# hbs.net
KiCad netlist of a schematic drawn in EAGLE
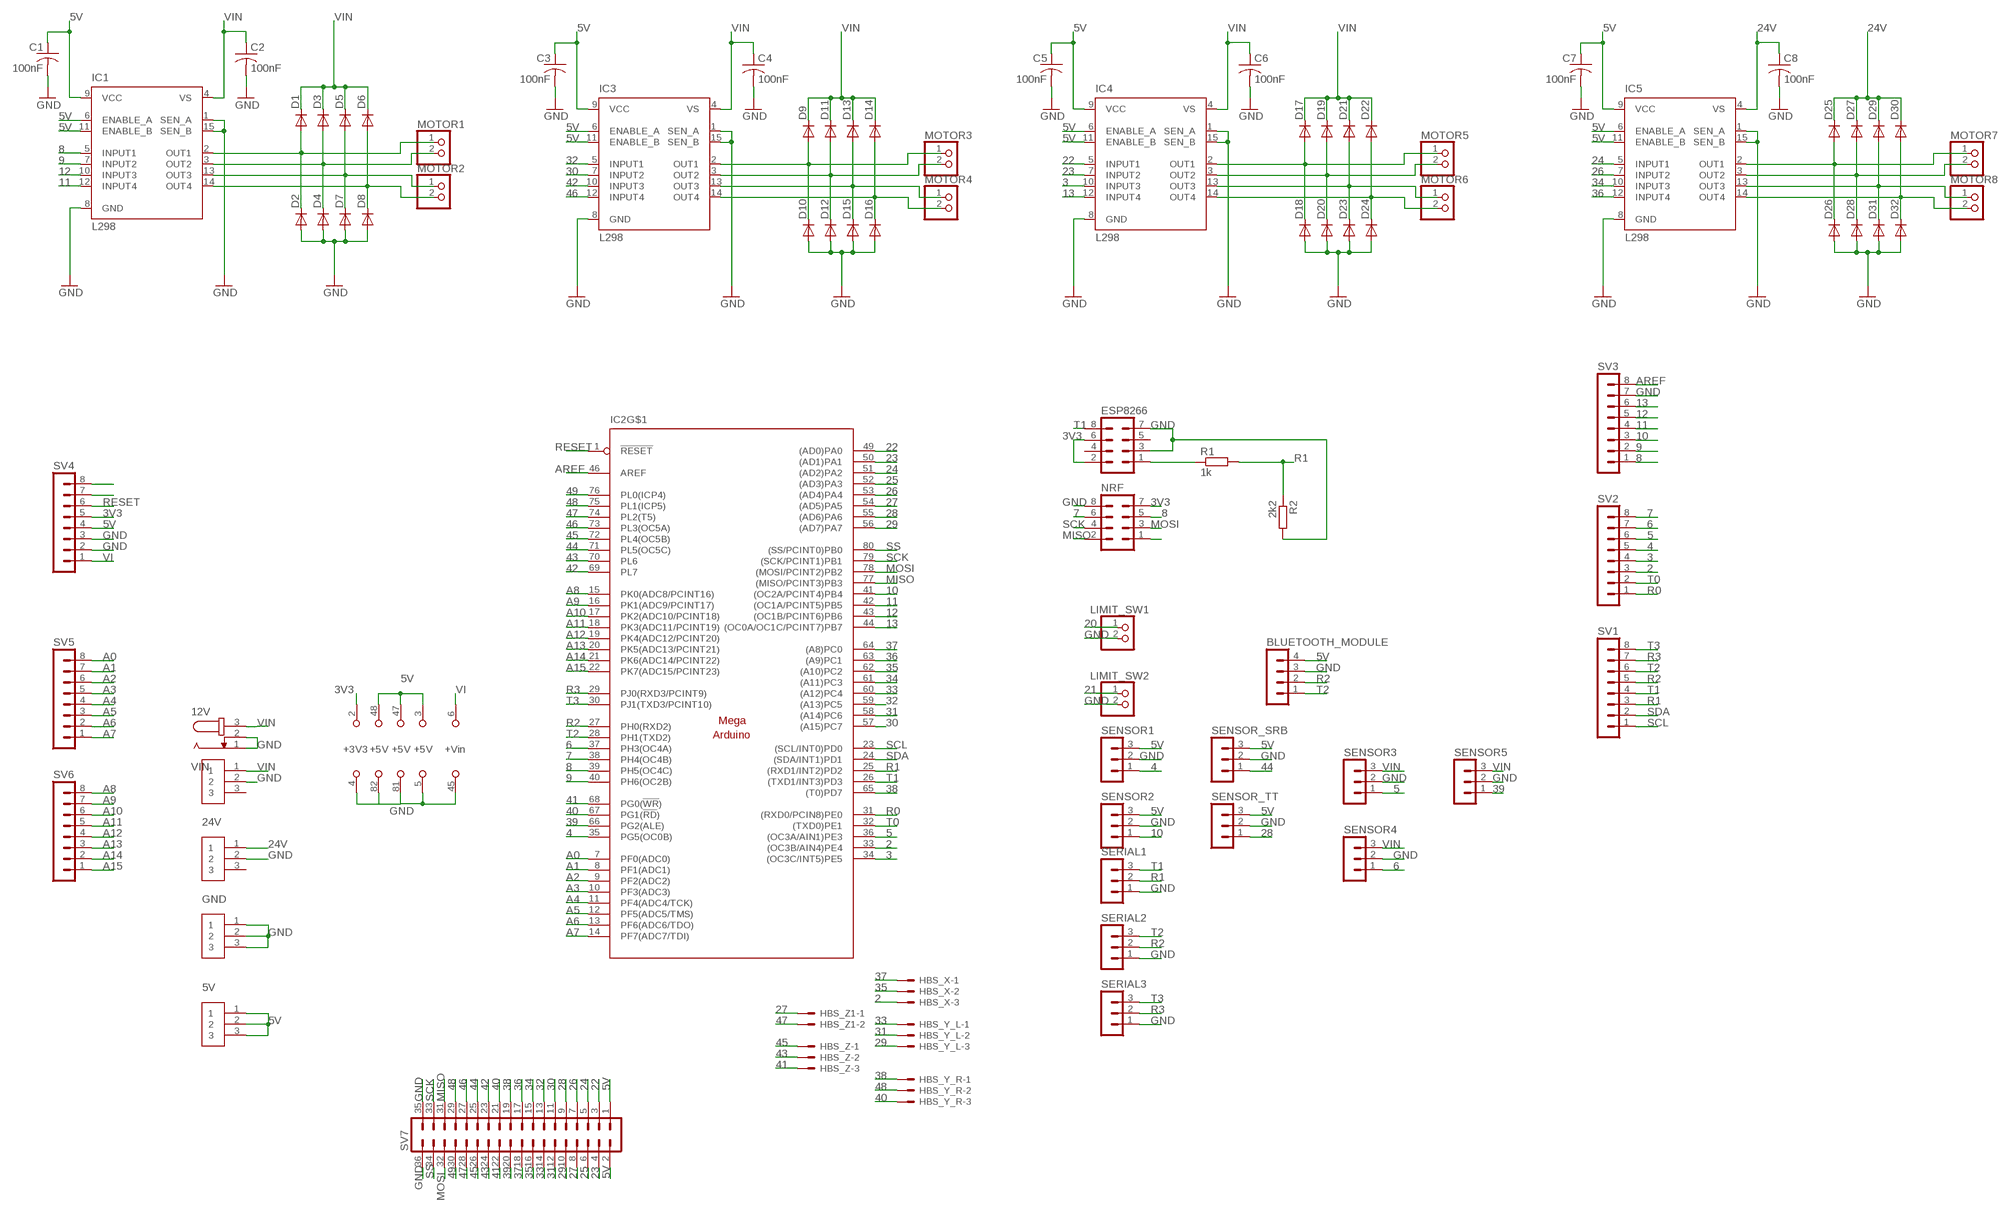
[diagram p0: schematic, sheet 1]

(export (version "E")
  (design (tool "Eeschema 10.0.6"))
  (components
    (comp (ref "5V")
      (value "691311500003")
      (footprint "eagle-import:TERMINALBLOCK_PLUGGABLE-3-5.08MM")
      (fields
        (field (name "DIGIKEY_PART_NO") "732-2053-ND")
        (field (name "MANUFACTURER") "WURTH ELEKTRONIK")
        (field (name "CREATED_BY") "PCBLayout.com")
      )
      (libsource (lib "eagle-import") (part "691311500003"))
    )
    (comp (ref "12V")
      (value "JACK-PLUG0")
      (footprint "eagle-import:SPC4077")
      (libsource (lib "eagle-import") (part "JACK-PLUG0"))
    )
    (comp (ref "24V")
      (value "691311500003")
      (footprint "eagle-import:TERMINALBLOCK_PLUGGABLE-3-5.08MM")
      (fields
        (field (name "DIGIKEY_PART_NO") "732-2053-ND")
        (field (name "MANUFACTURER") "WURTH ELEKTRONIK")
        (field (name "CREATED_BY") "PCBLayout.com")
      )
      (libsource (lib "eagle-import") (part "691311500003"))
    )
    (comp (ref "BLUETOOTH_MODULE")
      (value "MA04-1")
      (footprint "eagle-import:MA04-1")
      (libsource (lib "eagle-import") (part "MA04-1"))
    )
    (comp (ref "C1")
      (value "100nF")
      (footprint "eagle-import:C050-024X044")
      (libsource (lib "eagle-import") (part "C-US050-024X044"))
    )
    (comp (ref "C2")
      (value "100nF")
      (footprint "eagle-import:C050-024X044")
      (libsource (lib "eagle-import") (part "C-US050-024X044"))
    )
    (comp (ref "C3")
      (value "100nF")
      (footprint "eagle-import:C050-024X044")
      (libsource (lib "eagle-import") (part "C-US050-024X044"))
    )
    (comp (ref "C4")
      (value "100nF")
      (footprint "eagle-import:C050-024X044")
      (libsource (lib "eagle-import") (part "C-US050-024X044"))
    )
    (comp (ref "C5")
      (value "100nF")
      (footprint "eagle-import:C050-024X044")
      (libsource (lib "eagle-import") (part "C-US050-024X044"))
    )
    (comp (ref "C6")
      (value "100nF")
      (footprint "eagle-import:C050-024X044")
      (libsource (lib "eagle-import") (part "C-US050-024X044"))
    )
    (comp (ref "C7")
      (value "100nF")
      (footprint "eagle-import:C050-024X044")
      (libsource (lib "eagle-import") (part "C-US050-024X044"))
    )
    (comp (ref "C8")
      (value "100nF")
      (footprint "eagle-import:C050-024X044")
      (libsource (lib "eagle-import") (part "C-US050-024X044"))
    )
    (comp (ref "D1")
      (value "DIODE-D-5")
      (footprint "eagle-import:D-5")
      (libsource (lib "eagle-import") (part "DIODE-D-5"))
    )
    (comp (ref "D2")
      (value "DIODE-D-5")
      (footprint "eagle-import:D-5")
      (libsource (lib "eagle-import") (part "DIODE-D-5"))
    )
    (comp (ref "D3")
      (value "DIODE-D-5")
      (footprint "eagle-import:D-5")
      (libsource (lib "eagle-import") (part "DIODE-D-5"))
    )
    (comp (ref "D4")
      (value "DIODE-D-5")
      (footprint "eagle-import:D-5")
      (libsource (lib "eagle-import") (part "DIODE-D-5"))
    )
    (comp (ref "D5")
      (value "DIODE-D-5")
      (footprint "eagle-import:D-5")
      (libsource (lib "eagle-import") (part "DIODE-D-5"))
    )
    (comp (ref "D6")
      (value "DIODE-D-5")
      (footprint "eagle-import:D-5")
      (libsource (lib "eagle-import") (part "DIODE-D-5"))
    )
    (comp (ref "D7")
      (value "DIODE-D-5")
      (footprint "eagle-import:D-5")
      (libsource (lib "eagle-import") (part "DIODE-D-5"))
    )
    (comp (ref "D8")
      (value "DIODE-D-5")
      (footprint "eagle-import:D-5")
      (libsource (lib "eagle-import") (part "DIODE-D-5"))
    )
    (comp (ref "D9")
      (value "DIODE-D-5")
      (footprint "eagle-import:D-5")
      (libsource (lib "eagle-import") (part "DIODE-D-5"))
    )
    (comp (ref "D10")
      (value "DIODE-D-5")
      (footprint "eagle-import:D-5")
      (libsource (lib "eagle-import") (part "DIODE-D-5"))
    )
    (comp (ref "D11")
      (value "DIODE-D-5")
      (footprint "eagle-import:D-5")
      (libsource (lib "eagle-import") (part "DIODE-D-5"))
    )
    (comp (ref "D12")
      (value "DIODE-D-5")
      (footprint "eagle-import:D-5")
      (libsource (lib "eagle-import") (part "DIODE-D-5"))
    )
    (comp (ref "D13")
      (value "DIODE-D-5")
      (footprint "eagle-import:D-5")
      (libsource (lib "eagle-import") (part "DIODE-D-5"))
    )
    (comp (ref "D14")
      (value "DIODE-D-5")
      (footprint "eagle-import:D-5")
      (libsource (lib "eagle-import") (part "DIODE-D-5"))
    )
    (comp (ref "D15")
      (value "DIODE-D-5")
      (footprint "eagle-import:D-5")
      (libsource (lib "eagle-import") (part "DIODE-D-5"))
    )
    (comp (ref "D16")
      (value "DIODE-D-5")
      (footprint "eagle-import:D-5")
      (libsource (lib "eagle-import") (part "DIODE-D-5"))
    )
    (comp (ref "D17")
      (value "DIODE-D-5")
      (footprint "eagle-import:D-5")
      (libsource (lib "eagle-import") (part "DIODE-D-5"))
    )
    (comp (ref "D18")
      (value "DIODE-D-5")
      (footprint "eagle-import:D-5")
      (libsource (lib "eagle-import") (part "DIODE-D-5"))
    )
    (comp (ref "D19")
      (value "DIODE-D-5")
      (footprint "eagle-import:D-5")
      (libsource (lib "eagle-import") (part "DIODE-D-5"))
    )
    (comp (ref "D20")
      (value "DIODE-D-5")
      (footprint "eagle-import:D-5")
      (libsource (lib "eagle-import") (part "DIODE-D-5"))
    )
    (comp (ref "D21")
      (value "DIODE-D-5")
      (footprint "eagle-import:D-5")
      (libsource (lib "eagle-import") (part "DIODE-D-5"))
    )
    (comp (ref "D22")
      (value "DIODE-D-5")
      (footprint "eagle-import:D-5")
      (libsource (lib "eagle-import") (part "DIODE-D-5"))
    )
    (comp (ref "D23")
      (value "DIODE-D-5")
      (footprint "eagle-import:D-5")
      (libsource (lib "eagle-import") (part "DIODE-D-5"))
    )
    (comp (ref "D24")
      (value "DIODE-D-5")
      (footprint "eagle-import:D-5")
      (libsource (lib "eagle-import") (part "DIODE-D-5"))
    )
    (comp (ref "D25")
      (value "DIODE-D-5")
      (footprint "eagle-import:D-5")
      (libsource (lib "eagle-import") (part "DIODE-D-5"))
    )
    (comp (ref "D26")
      (value "DIODE-D-5")
      (footprint "eagle-import:D-5")
      (libsource (lib "eagle-import") (part "DIODE-D-5"))
    )
    (comp (ref "D27")
      (value "DIODE-D-5")
      (footprint "eagle-import:D-5")
      (libsource (lib "eagle-import") (part "DIODE-D-5"))
    )
    (comp (ref "D28")
      (value "DIODE-D-5")
      (footprint "eagle-import:D-5")
      (libsource (lib "eagle-import") (part "DIODE-D-5"))
    )
    (comp (ref "D29")
      (value "DIODE-D-5")
      (footprint "eagle-import:D-5")
      (libsource (lib "eagle-import") (part "DIODE-D-5"))
    )
    (comp (ref "D30")
      (value "DIODE-D-5")
      (footprint "eagle-import:D-5")
      (libsource (lib "eagle-import") (part "DIODE-D-5"))
    )
    (comp (ref "D31")
      (value "DIODE-D-5")
      (footprint "eagle-import:D-5")
      (libsource (lib "eagle-import") (part "DIODE-D-5"))
    )
    (comp (ref "D32")
      (value "DIODE-D-5")
      (footprint "eagle-import:D-5")
      (libsource (lib "eagle-import") (part "DIODE-D-5"))
    )
    (comp (ref "ESP8266")
      (value "MA04-2")
      (footprint "eagle-import:MA04-2")
      (libsource (lib "eagle-import") (part "MA04-2"))
    )
    (comp (ref "GND")
      (value "691311500003")
      (footprint "eagle-import:TERMINALBLOCK_PLUGGABLE-3-5.08MM")
      (fields
        (field (name "DIGIKEY_PART_NO") "732-2053-ND")
        (field (name "MANUFACTURER") "WURTH ELEKTRONIK")
        (field (name "CREATED_BY") "PCBLayout.com")
      )
      (libsource (lib "eagle-import") (part "691311500003"))
    )
    (comp (ref "HBS_X")
      (value "JST-XH-03-PIN-LONG-PAD")
      (footprint "eagle-import:JST-XH-03-PACKAGE-LONG-PAD")
      (libsource (lib "eagle-import") (part "JST-XH-03-PIN-LONG-PAD"))
    )
    (comp (ref "HBS_Y_L")
      (value "JST-XH-03-PIN-LONG-PAD")
      (footprint "eagle-import:JST-XH-03-PACKAGE-LONG-PAD")
      (libsource (lib "eagle-import") (part "JST-XH-03-PIN-LONG-PAD"))
    )
    (comp (ref "HBS_Y_R")
      (value "JST-XH-03-PIN-LONG-PAD")
      (footprint "eagle-import:JST-XH-03-PACKAGE-LONG-PAD")
      (libsource (lib "eagle-import") (part "JST-XH-03-PIN-LONG-PAD"))
    )
    (comp (ref "HBS_Z")
      (value "JST-XH-03-PIN-LONG-PAD")
      (footprint "eagle-import:JST-XH-03-PACKAGE-LONG-PAD")
      (libsource (lib "eagle-import") (part "JST-XH-03-PIN-LONG-PAD"))
    )
    (comp (ref "HBS_Z1")
      (value "JST-XH-02-PIN-LONG-PAD")
      (footprint "eagle-import:JST-XH-02-PACKAGE-LONG-PAD")
      (libsource (lib "eagle-import") (part "JST-XH-02-PIN-LONG-PAD"))
    )
    (comp (ref "IC1")
      (value "L298")
      (footprint "eagle-import:MULTIWATT-15")
      (fields (field (name "MPN") "L298N"))
      (libsource (lib "eagle-import") (part "L298"))
    )
    (comp (ref "IC2")
      (value "MEGAARDUINO_21")
      (footprint "eagle-import:MEGA_ARDUINO_1")
      (libsource (lib "eagle-import") (part "MEGAARDUINO_21"))
    )
    (comp (ref "IC3")
      (value "L298")
      (footprint "eagle-import:MULTIWATT-15")
      (fields (field (name "MPN") "L298N"))
      (libsource (lib "eagle-import") (part "L298"))
    )
    (comp (ref "IC4")
      (value "L298")
      (footprint "eagle-import:MULTIWATT-15")
      (fields (field (name "MPN") "L298N"))
      (libsource (lib "eagle-import") (part "L298"))
    )
    (comp (ref "IC5")
      (value "L298")
      (footprint "eagle-import:MULTIWATT-15")
      (fields (field (name "MPN") "L298N"))
      (libsource (lib "eagle-import") (part "L298"))
    )
    (comp (ref "LIMIT_SW1")
      (value "PINHD-1X2")
      (footprint "eagle-import:1X02")
      (libsource (lib "eagle-import") (part "PINHD-1X2"))
    )
    (comp (ref "LIMIT_SW2")
      (value "PINHD-1X2")
      (footprint "eagle-import:1X02")
      (libsource (lib "eagle-import") (part "PINHD-1X2"))
    )
    (comp (ref "MOTOR1")
      (value "PINHD-1X2")
      (footprint "eagle-import:1X02")
      (libsource (lib "eagle-import") (part "PINHD-1X2"))
    )
    (comp (ref "MOTOR2")
      (value "PINHD-1X2")
      (footprint "eagle-import:1X02")
      (libsource (lib "eagle-import") (part "PINHD-1X2"))
    )
    (comp (ref "MOTOR3")
      (value "PINHD-1X2")
      (footprint "eagle-import:1X02")
      (libsource (lib "eagle-import") (part "PINHD-1X2"))
    )
    (comp (ref "MOTOR4")
      (value "PINHD-1X2")
      (footprint "eagle-import:1X02")
      (libsource (lib "eagle-import") (part "PINHD-1X2"))
    )
    (comp (ref "MOTOR5")
      (value "PINHD-1X2")
      (footprint "eagle-import:1X02")
      (libsource (lib "eagle-import") (part "PINHD-1X2"))
    )
    (comp (ref "MOTOR6")
      (value "PINHD-1X2")
      (footprint "eagle-import:1X02")
      (libsource (lib "eagle-import") (part "PINHD-1X2"))
    )
    (comp (ref "MOTOR7")
      (value "PINHD-1X2")
      (footprint "eagle-import:1X02")
      (libsource (lib "eagle-import") (part "PINHD-1X2"))
    )
    (comp (ref "MOTOR8")
      (value "PINHD-1X2")
      (footprint "eagle-import:1X02")
      (libsource (lib "eagle-import") (part "PINHD-1X2"))
    )
    (comp (ref "NRF")
      (value "MA04-2")
      (footprint "eagle-import:MA04-2")
      (libsource (lib "eagle-import") (part "MA04-2"))
    )
    (comp (ref "R1")
      (value "1k")
      (footprint "eagle-import:0204_7")
      (libsource (lib "eagle-import") (part "R-EU_0204/7"))
    )
    (comp (ref "R2")
      (value "2k2")
      (footprint "eagle-import:0204_7")
      (libsource (lib "eagle-import") (part "R-EU_0204/7"))
    )
    (comp (ref "SENSOR1")
      (value "MA03-1")
      (footprint "eagle-import:MA03-1")
      (libsource (lib "eagle-import") (part "MA03-1"))
    )
    (comp (ref "SENSOR2")
      (value "MA03-1")
      (footprint "eagle-import:MA03-1")
      (libsource (lib "eagle-import") (part "MA03-1"))
    )
    (comp (ref "SENSOR3")
      (value "MA03-1")
      (footprint "eagle-import:MA03-1")
      (libsource (lib "eagle-import") (part "MA03-1"))
    )
    (comp (ref "SENSOR4")
      (value "MA03-1")
      (footprint "eagle-import:MA03-1")
      (libsource (lib "eagle-import") (part "MA03-1"))
    )
    (comp (ref "SENSOR5")
      (value "MA03-1")
      (footprint "eagle-import:MA03-1")
      (libsource (lib "eagle-import") (part "MA03-1"))
    )
    (comp (ref "SENSOR_SRB")
      (value "MA03-1")
      (footprint "eagle-import:MA03-1")
      (libsource (lib "eagle-import") (part "MA03-1"))
    )
    (comp (ref "SENSOR_TT")
      (value "MA03-1")
      (footprint "eagle-import:MA03-1")
      (libsource (lib "eagle-import") (part "MA03-1"))
    )
    (comp (ref "SERIAL1")
      (value "MA03-1")
      (footprint "eagle-import:MA03-1")
      (libsource (lib "eagle-import") (part "MA03-1"))
    )
    (comp (ref "SERIAL2")
      (value "MA03-1")
      (footprint "eagle-import:MA03-1")
      (libsource (lib "eagle-import") (part "MA03-1"))
    )
    (comp (ref "SERIAL3")
      (value "MA03-1")
      (footprint "eagle-import:MA03-1")
      (libsource (lib "eagle-import") (part "MA03-1"))
    )
    (comp (ref "SV1")
      (value "MA08-1")
      (footprint "eagle-import:MA08-1")
      (libsource (lib "eagle-import") (part "MA08-1"))
    )
    (comp (ref "SV2")
      (value "MA08-1")
      (footprint "eagle-import:MA08-1")
      (libsource (lib "eagle-import") (part "MA08-1"))
    )
    (comp (ref "SV3")
      (value "MA08-1")
      (footprint "eagle-import:MA08-1")
      (libsource (lib "eagle-import") (part "MA08-1"))
    )
    (comp (ref "SV4")
      (value "MA08-1")
      (footprint "eagle-import:MA08-1")
      (libsource (lib "eagle-import") (part "MA08-1"))
    )
    (comp (ref "SV5")
      (value "MA08-1")
      (footprint "eagle-import:MA08-1")
      (libsource (lib "eagle-import") (part "MA08-1"))
    )
    (comp (ref "SV6")
      (value "MA08-1")
      (footprint "eagle-import:MA08-1")
      (libsource (lib "eagle-import") (part "MA08-1"))
    )
    (comp (ref "SV7")
      (value "MA18-2")
      (footprint "eagle-import:MA18-2")
      (libsource (lib "eagle-import") (part "MA18-2"))
    )
    (comp (ref "VIN")
      (value "691311500003")
      (footprint "eagle-import:TERMINALBLOCK_PLUGGABLE-3-5.08MM")
      (fields
        (field (name "DIGIKEY_PART_NO") "732-2053-ND")
        (field (name "MANUFACTURER") "WURTH ELEKTRONIK")
        (field (name "CREATED_BY") "PCBLayout.com")
      )
      (libsource (lib "eagle-import") (part "691311500003"))
    )
  )
  (nets
    (net (code "1") (name "/2") (class "Default")
      (node (ref "HBS_X") (pin "3") (pinfunction "S_3") (pintype "passive"))
      (node (ref "IC2") (pin "33") (pinfunction "(OC3B/AIN4)PE4_33") (pintype "bidirectional"))
      (node (ref "SV2") (pin "3") (pinfunction "3_3") (pintype "passive"))
    )
    (net (code "2") (name "/3") (class "Default")
      (node (ref "IC2") (pin "34") (pinfunction "(OC3C/INT5)PE5_34") (pintype "bidirectional"))
      (node (ref "IC4") (pin "10") (pinfunction "INPUT3_10") (pintype "input"))
      (node (ref "SV2") (pin "4") (pinfunction "4_4") (pintype "passive"))
    )
    (net (code "3") (name "/3V3") (class "Default")
      (node (ref "ESP8266") (pin "2") (pinfunction "2_2") (pintype "passive"))
      (node (ref "ESP8266") (pin "6") (pinfunction "6_6") (pintype "passive"))
      (node (ref "IC2") (pin "2") (pinfunction "+3V3_2") (pintype "power_in"))
      (node (ref "NRF") (pin "7") (pinfunction "7_7") (pintype "passive"))
      (node (ref "SV4") (pin "5") (pinfunction "5_5") (pintype "passive"))
    )
    (net (code "4") (name "/4") (class "Default")
      (node (ref "IC2") (pin "35") (pinfunction "PG5(OC0B)_35") (pintype "bidirectional"))
      (node (ref "SENSOR1") (pin "1") (pinfunction "1_1") (pintype "passive"))
      (node (ref "SV2") (pin "5") (pinfunction "5_5") (pintype "passive"))
    )
    (net (code "5") (name "/5") (class "Default")
      (node (ref "IC2") (pin "36") (pinfunction "(OC3A/AIN1)PE3_36") (pintype "bidirectional"))
      (node (ref "SENSOR3") (pin "1") (pinfunction "1_1") (pintype "passive"))
      (node (ref "SV2") (pin "6") (pinfunction "6_6") (pintype "passive"))
    )
    (net (code "6") (name "/5V") (class "Default")
      (node (ref "5V") (pin "1") (pinfunction "1_1") (pintype "passive"))
      (node (ref "5V") (pin "2") (pinfunction "2_2") (pintype "passive"))
      (node (ref "5V") (pin "3") (pinfunction "3_3") (pintype "passive"))
      (node (ref "BLUETOOTH_MODULE") (pin "4") (pinfunction "4_4") (pintype "passive"))
      (node (ref "C1") (pin "1") (pinfunction "1_1") (pintype "passive"))
      (node (ref "C3") (pin "1") (pinfunction "1_1") (pintype "passive"))
      (node (ref "C5") (pin "1") (pinfunction "1_1") (pintype "passive"))
      (node (ref "C7") (pin "1") (pinfunction "1_1") (pintype "passive"))
      (node (ref "IC1") (pin "11") (pinfunction "ENABLE_B_11") (pintype "input"))
      (node (ref "IC1") (pin "6") (pinfunction "ENABLE_A_6") (pintype "input"))
      (node (ref "IC1") (pin "9") (pinfunction "VCC_9") (pintype "power_in"))
      (node (ref "IC2") (pin "3") (pinfunction "+5V_3") (pintype "power_in"))
      (node (ref "IC2") (pin "47") (pinfunction "+5V_47") (pintype "power_in"))
      (node (ref "IC2") (pin "48") (pinfunction "+5V_48") (pintype "power_in"))
      (node (ref "IC3") (pin "11") (pinfunction "ENABLE_B_11") (pintype "input"))
      (node (ref "IC3") (pin "6") (pinfunction "ENABLE_A_6") (pintype "input"))
      (node (ref "IC3") (pin "9") (pinfunction "VCC_9") (pintype "power_in"))
      (node (ref "IC4") (pin "11") (pinfunction "ENABLE_B_11") (pintype "input"))
      (node (ref "IC4") (pin "6") (pinfunction "ENABLE_A_6") (pintype "input"))
      (node (ref "IC4") (pin "9") (pinfunction "VCC_9") (pintype "power_in"))
      (node (ref "IC5") (pin "11") (pinfunction "ENABLE_B_11") (pintype "input"))
      (node (ref "IC5") (pin "6") (pinfunction "ENABLE_A_6") (pintype "input"))
      (node (ref "IC5") (pin "9") (pinfunction "VCC_9") (pintype "power_in"))
      (node (ref "SENSOR1") (pin "3") (pinfunction "3_3") (pintype "passive"))
      (node (ref "SENSOR2") (pin "3") (pinfunction "3_3") (pintype "passive"))
      (node (ref "SENSOR_SRB") (pin "3") (pinfunction "3_3") (pintype "passive"))
      (node (ref "SENSOR_TT") (pin "3") (pinfunction "3_3") (pintype "passive"))
      (node (ref "SV4") (pin "4") (pinfunction "4_4") (pintype "passive"))
      (node (ref "SV7") (pin "1") (pinfunction "1_1") (pintype "passive"))
      (node (ref "SV7") (pin "2") (pinfunction "2_2") (pintype "passive"))
    )
    (net (code "7") (name "/6") (class "Default")
      (node (ref "IC2") (pin "37") (pinfunction "PH3(OC4A)_37") (pintype "bidirectional"))
      (node (ref "SENSOR4") (pin "1") (pinfunction "1_1") (pintype "passive"))
      (node (ref "SV2") (pin "7") (pinfunction "7_7") (pintype "passive"))
    )
    (net (code "8") (name "/7") (class "Default")
      (node (ref "IC2") (pin "38") (pinfunction "PH4(OC4B)_38") (pintype "bidirectional"))
      (node (ref "NRF") (pin "6") (pinfunction "6_6") (pintype "passive"))
      (node (ref "SV2") (pin "8") (pinfunction "8_8") (pintype "passive"))
    )
    (net (code "9") (name "/8") (class "Default")
      (node (ref "IC1") (pin "5") (pinfunction "INPUT1_5") (pintype "input"))
      (node (ref "IC2") (pin "39") (pinfunction "PH5(OC4C)_39") (pintype "bidirectional"))
      (node (ref "NRF") (pin "5") (pinfunction "5_5") (pintype "passive"))
      (node (ref "SV3") (pin "1") (pinfunction "1_1") (pintype "passive"))
    )
    (net (code "10") (name "/9") (class "Default")
      (node (ref "IC1") (pin "7") (pinfunction "INPUT2_7") (pintype "input"))
      (node (ref "IC2") (pin "40") (pinfunction "PH6(OC2B)_40") (pintype "bidirectional"))
      (node (ref "SV3") (pin "2") (pinfunction "2_2") (pintype "passive"))
    )
    (net (code "11") (name "/10") (class "Default")
      (node (ref "IC2") (pin "41") (pinfunction "(OC2A/PCINT4)PB4_41") (pintype "bidirectional"))
      (node (ref "SENSOR2") (pin "1") (pinfunction "1_1") (pintype "passive"))
      (node (ref "SV3") (pin "3") (pinfunction "3_3") (pintype "passive"))
    )
    (net (code "12") (name "/11") (class "Default")
      (node (ref "IC1") (pin "12") (pinfunction "INPUT4_12") (pintype "input"))
      (node (ref "IC2") (pin "42") (pinfunction "(OC1A/PCINT5)PB5_42") (pintype "bidirectional"))
      (node (ref "SV3") (pin "4") (pinfunction "4_4") (pintype "passive"))
    )
    (net (code "13") (name "/12") (class "Default")
      (node (ref "IC1") (pin "10") (pinfunction "INPUT3_10") (pintype "input"))
      (node (ref "IC2") (pin "43") (pinfunction "(OC1B/PCINT6)PB6_43") (pintype "bidirectional"))
      (node (ref "SV3") (pin "5") (pinfunction "5_5") (pintype "passive"))
    )
    (net (code "14") (name "/13") (class "Default")
      (node (ref "IC2") (pin "44") (pinfunction "(OC0A/OC1C/PCINT7)PB7_44") (pintype "bidirectional"))
      (node (ref "IC4") (pin "12") (pinfunction "INPUT4_12") (pintype "input"))
      (node (ref "SV3") (pin "6") (pinfunction "6_6") (pintype "passive"))
    )
    (net (code "15") (name "/20") (class "Default")
      (node (ref "LIMIT_SW1") (pin "1") (pinfunction "1_1") (pintype "passive"))
    )
    (net (code "16") (name "/21") (class "Default")
      (node (ref "LIMIT_SW2") (pin "1") (pinfunction "1_1") (pintype "passive"))
    )
    (net (code "17") (name "/22") (class "Default")
      (node (ref "IC2") (pin "49") (pinfunction "(AD0)PA0_49") (pintype "bidirectional"))
      (node (ref "IC4") (pin "5") (pinfunction "INPUT1_5") (pintype "input"))
      (node (ref "SV7") (pin "3") (pinfunction "3_3") (pintype "passive"))
    )
    (net (code "18") (name "/23") (class "Default")
      (node (ref "IC2") (pin "50") (pinfunction "(AD1)PA1_50") (pintype "bidirectional"))
      (node (ref "IC4") (pin "7") (pinfunction "INPUT2_7") (pintype "input"))
      (node (ref "SV7") (pin "4") (pinfunction "4_4") (pintype "passive"))
    )
    (net (code "19") (name "/24") (class "Default")
      (node (ref "IC2") (pin "51") (pinfunction "(AD2)PA2_51") (pintype "bidirectional"))
      (node (ref "IC5") (pin "5") (pinfunction "INPUT1_5") (pintype "input"))
      (node (ref "SV7") (pin "5") (pinfunction "5_5") (pintype "passive"))
    )
    (net (code "20") (name "/24V") (class "Default")
      (node (ref "24V") (pin "1") (pinfunction "1_1") (pintype "passive"))
      (node (ref "C8") (pin "1") (pinfunction "1_1") (pintype "passive"))
      (node (ref "D25") (pin "C") (pinfunction "C_C") (pintype "passive"))
      (node (ref "D27") (pin "C") (pinfunction "C_C") (pintype "passive"))
      (node (ref "D29") (pin "C") (pinfunction "C_C") (pintype "passive"))
      (node (ref "D30") (pin "C") (pinfunction "C_C") (pintype "passive"))
      (node (ref "IC5") (pin "4") (pinfunction "VS_4") (pintype "power_in"))
    )
    (net (code "21") (name "/25") (class "Default")
      (node (ref "IC2") (pin "52") (pinfunction "(AD3)PA3_52") (pintype "bidirectional"))
      (node (ref "SV7") (pin "6") (pinfunction "6_6") (pintype "passive"))
    )
    (net (code "22") (name "/26") (class "Default")
      (node (ref "IC2") (pin "53") (pinfunction "(AD4)PA4_53") (pintype "bidirectional"))
      (node (ref "IC5") (pin "7") (pinfunction "INPUT2_7") (pintype "input"))
      (node (ref "SV7") (pin "7") (pinfunction "7_7") (pintype "passive"))
    )
    (net (code "23") (name "/27") (class "Default")
      (node (ref "HBS_Z1") (pin "1") (pinfunction "S_1") (pintype "passive"))
      (node (ref "IC2") (pin "54") (pinfunction "(AD5)PA5_54") (pintype "bidirectional"))
      (node (ref "SV7") (pin "8") (pinfunction "8_8") (pintype "passive"))
    )
    (net (code "24") (name "/28") (class "Default")
      (node (ref "IC2") (pin "55") (pinfunction "(AD6)PA6_55") (pintype "bidirectional"))
      (node (ref "SENSOR_TT") (pin "1") (pinfunction "1_1") (pintype "passive"))
      (node (ref "SV7") (pin "9") (pinfunction "9_9") (pintype "passive"))
    )
    (net (code "25") (name "/29") (class "Default")
      (node (ref "HBS_Y_L") (pin "3") (pinfunction "S_3") (pintype "passive"))
      (node (ref "IC2") (pin "56") (pinfunction "(AD7)PA7_56") (pintype "bidirectional"))
      (node (ref "SV7") (pin "10") (pinfunction "10_10") (pintype "passive"))
    )
    (net (code "26") (name "/30") (class "Default")
      (node (ref "IC2") (pin "57") (pinfunction "(A15)PC7_57") (pintype "bidirectional"))
      (node (ref "IC3") (pin "7") (pinfunction "INPUT2_7") (pintype "input"))
      (node (ref "SV7") (pin "11") (pinfunction "11_11") (pintype "passive"))
    )
    (net (code "27") (name "/31") (class "Default")
      (node (ref "HBS_Y_L") (pin "2") (pinfunction "S_2") (pintype "passive"))
      (node (ref "IC2") (pin "58") (pinfunction "(A14)PC6_58") (pintype "bidirectional"))
      (node (ref "SV7") (pin "12") (pinfunction "12_12") (pintype "passive"))
    )
    (net (code "28") (name "/32") (class "Default")
      (node (ref "IC2") (pin "59") (pinfunction "(A13)PC5_59") (pintype "bidirectional"))
      (node (ref "IC3") (pin "5") (pinfunction "INPUT1_5") (pintype "input"))
      (node (ref "SV7") (pin "13") (pinfunction "13_13") (pintype "passive"))
    )
    (net (code "29") (name "/33") (class "Default")
      (node (ref "HBS_Y_L") (pin "1") (pinfunction "S_1") (pintype "passive"))
      (node (ref "IC2") (pin "60") (pinfunction "(A12)PC4_60") (pintype "bidirectional"))
      (node (ref "SV7") (pin "14") (pinfunction "14_14") (pintype "passive"))
    )
    (net (code "30") (name "/34") (class "Default")
      (node (ref "IC2") (pin "61") (pinfunction "(A11)PC3_61") (pintype "bidirectional"))
      (node (ref "IC5") (pin "10") (pinfunction "INPUT3_10") (pintype "input"))
      (node (ref "SV7") (pin "15") (pinfunction "15_15") (pintype "passive"))
    )
    (net (code "31") (name "/35") (class "Default")
      (node (ref "HBS_X") (pin "2") (pinfunction "S_2") (pintype "passive"))
      (node (ref "IC2") (pin "62") (pinfunction "(A10)PC2_62") (pintype "bidirectional"))
      (node (ref "SV7") (pin "16") (pinfunction "16_16") (pintype "passive"))
    )
    (net (code "32") (name "/36") (class "Default")
      (node (ref "IC2") (pin "63") (pinfunction "(A9)PC1_63") (pintype "bidirectional"))
      (node (ref "IC5") (pin "12") (pinfunction "INPUT4_12") (pintype "input"))
      (node (ref "SV7") (pin "17") (pinfunction "17_17") (pintype "passive"))
    )
    (net (code "33") (name "/37") (class "Default")
      (node (ref "HBS_X") (pin "1") (pinfunction "S_1") (pintype "passive"))
      (node (ref "IC2") (pin "64") (pinfunction "(A8)PC0_64") (pintype "bidirectional"))
      (node (ref "SV7") (pin "18") (pinfunction "18_18") (pintype "passive"))
    )
    (net (code "34") (name "/38") (class "Default")
      (node (ref "HBS_Y_R") (pin "1") (pinfunction "S_1") (pintype "passive"))
      (node (ref "IC2") (pin "65") (pinfunction "(T0)PD7_65") (pintype "bidirectional"))
      (node (ref "SV7") (pin "19") (pinfunction "19_19") (pintype "passive"))
    )
    (net (code "35") (name "/39") (class "Default")
      (node (ref "IC2") (pin "66") (pinfunction "PG2(ALE)_66") (pintype "bidirectional"))
      (node (ref "SENSOR5") (pin "1") (pinfunction "1_1") (pintype "passive"))
      (node (ref "SV7") (pin "20") (pinfunction "20_20") (pintype "passive"))
    )
    (net (code "36") (name "/40") (class "Default")
      (node (ref "HBS_Y_R") (pin "3") (pinfunction "S_3") (pintype "passive"))
      (node (ref "IC2") (pin "67") (pinfunction "PG1(~{RD})_67") (pintype "bidirectional"))
      (node (ref "SV7") (pin "21") (pinfunction "21_21") (pintype "passive"))
    )
    (net (code "37") (name "/41") (class "Default")
      (node (ref "HBS_Z") (pin "3") (pinfunction "S_3") (pintype "passive"))
      (node (ref "IC2") (pin "68") (pinfunction "PG0(~{WR})_68") (pintype "bidirectional"))
      (node (ref "SV7") (pin "22") (pinfunction "22_22") (pintype "passive"))
    )
    (net (code "38") (name "/42") (class "Default")
      (node (ref "IC2") (pin "69") (pinfunction "PL7_69") (pintype "bidirectional"))
      (node (ref "IC3") (pin "10") (pinfunction "INPUT3_10") (pintype "input"))
      (node (ref "SV7") (pin "23") (pinfunction "23_23") (pintype "passive"))
    )
    (net (code "39") (name "/43") (class "Default")
      (node (ref "HBS_Z") (pin "2") (pinfunction "S_2") (pintype "passive"))
      (node (ref "IC2") (pin "70") (pinfunction "PL6_70") (pintype "bidirectional"))
      (node (ref "SV7") (pin "24") (pinfunction "24_24") (pintype "passive"))
    )
    (net (code "40") (name "/44") (class "Default")
      (node (ref "IC2") (pin "71") (pinfunction "PL5(OC5C)_71") (pintype "bidirectional"))
      (node (ref "SENSOR_SRB") (pin "1") (pinfunction "1_1") (pintype "passive"))
      (node (ref "SV7") (pin "25") (pinfunction "25_25") (pintype "passive"))
    )
    (net (code "41") (name "/45") (class "Default")
      (node (ref "HBS_Z") (pin "1") (pinfunction "S_1") (pintype "passive"))
      (node (ref "IC2") (pin "72") (pinfunction "PL4(OC5B)_72") (pintype "bidirectional"))
      (node (ref "SV7") (pin "26") (pinfunction "26_26") (pintype "passive"))
    )
    (net (code "42") (name "/46") (class "Default")
      (node (ref "IC2") (pin "73") (pinfunction "PL3(OC5A)_73") (pintype "bidirectional"))
      (node (ref "IC3") (pin "12") (pinfunction "INPUT4_12") (pintype "input"))
      (node (ref "SV7") (pin "27") (pinfunction "27_27") (pintype "passive"))
    )
    (net (code "43") (name "/47") (class "Default")
      (node (ref "HBS_Z1") (pin "2") (pinfunction "S_2") (pintype "passive"))
      (node (ref "IC2") (pin "74") (pinfunction "PL2(T5)_74") (pintype "bidirectional"))
      (node (ref "SV7") (pin "28") (pinfunction "28_28") (pintype "passive"))
    )
    (net (code "44") (name "/48") (class "Default")
      (node (ref "HBS_Y_R") (pin "2") (pinfunction "S_2") (pintype "passive"))
      (node (ref "IC2") (pin "75") (pinfunction "PL1(ICP5)_75") (pintype "bidirectional"))
      (node (ref "SV7") (pin "29") (pinfunction "29_29") (pintype "passive"))
    )
    (net (code "45") (name "/49") (class "Default")
      (node (ref "IC2") (pin "76") (pinfunction "PL0(ICP4)_76") (pintype "bidirectional"))
      (node (ref "SV7") (pin "30") (pinfunction "30_30") (pintype "passive"))
    )
    (net (code "46") (name "/A0") (class "Default")
      (node (ref "IC2") (pin "7") (pinfunction "PF0(ADC0)_7") (pintype "bidirectional"))
      (node (ref "SV5") (pin "8") (pinfunction "8_8") (pintype "passive"))
    )
    (net (code "47") (name "/A1") (class "Default")
      (node (ref "IC2") (pin "8") (pinfunction "PF1(ADC1)_8") (pintype "bidirectional"))
      (node (ref "SV5") (pin "7") (pinfunction "7_7") (pintype "passive"))
    )
    (net (code "48") (name "/A2") (class "Default")
      (node (ref "IC2") (pin "9") (pinfunction "PF2(ADC2)_9") (pintype "bidirectional"))
      (node (ref "SV5") (pin "6") (pinfunction "6_6") (pintype "passive"))
    )
    (net (code "49") (name "/A3") (class "Default")
      (node (ref "IC2") (pin "10") (pinfunction "PF3(ADC3)_10") (pintype "bidirectional"))
      (node (ref "SV5") (pin "5") (pinfunction "5_5") (pintype "passive"))
    )
    (net (code "50") (name "/A4") (class "Default")
      (node (ref "IC2") (pin "11") (pinfunction "PF4(ADC4/TCK)_11") (pintype "bidirectional"))
      (node (ref "SV5") (pin "4") (pinfunction "4_4") (pintype "passive"))
    )
    (net (code "51") (name "/A5") (class "Default")
      (node (ref "IC2") (pin "12") (pinfunction "PF5(ADC5/TMS)_12") (pintype "bidirectional"))
      (node (ref "SV5") (pin "3") (pinfunction "3_3") (pintype "passive"))
    )
    (net (code "52") (name "/A6") (class "Default")
      (node (ref "IC2") (pin "13") (pinfunction "PF6(ADC6/TDO)_13") (pintype "bidirectional"))
      (node (ref "SV5") (pin "2") (pinfunction "2_2") (pintype "passive"))
    )
    (net (code "53") (name "/A7") (class "Default")
      (node (ref "IC2") (pin "14") (pinfunction "PF7(ADC7/TDI)_14") (pintype "bidirectional"))
      (node (ref "SV5") (pin "1") (pinfunction "1_1") (pintype "passive"))
    )
    (net (code "54") (name "/A8") (class "Default")
      (node (ref "IC2") (pin "15") (pinfunction "PK0(ADC8/PCINT16)_15") (pintype "bidirectional"))
      (node (ref "SV6") (pin "8") (pinfunction "8_8") (pintype "passive"))
    )
    (net (code "55") (name "/A9") (class "Default")
      (node (ref "IC2") (pin "16") (pinfunction "PK1(ADC9/PCINT17)_16") (pintype "bidirectional"))
      (node (ref "SV6") (pin "7") (pinfunction "7_7") (pintype "passive"))
    )
    (net (code "56") (name "/A10") (class "Default")
      (node (ref "IC2") (pin "17") (pinfunction "PK2(ADC10/PCINT18)_17") (pintype "bidirectional"))
      (node (ref "SV6") (pin "6") (pinfunction "6_6") (pintype "passive"))
    )
    (net (code "57") (name "/A11") (class "Default")
      (node (ref "IC2") (pin "18") (pinfunction "PK3(ADC11/PCINT19)_18") (pintype "bidirectional"))
      (node (ref "SV6") (pin "5") (pinfunction "5_5") (pintype "passive"))
    )
    (net (code "58") (name "/A12") (class "Default")
      (node (ref "IC2") (pin "19") (pinfunction "PK4(ADC12/PCINT20)_19") (pintype "bidirectional"))
      (node (ref "SV6") (pin "4") (pinfunction "4_4") (pintype "passive"))
    )
    (net (code "59") (name "/A13") (class "Default")
      (node (ref "IC2") (pin "20") (pinfunction "PK5(ADC13/PCINT21)_20") (pintype "bidirectional"))
      (node (ref "SV6") (pin "3") (pinfunction "3_3") (pintype "passive"))
    )
    (net (code "60") (name "/A14") (class "Default")
      (node (ref "IC2") (pin "21") (pinfunction "PK6(ADC14/PCINT22)_21") (pintype "bidirectional"))
      (node (ref "SV6") (pin "2") (pinfunction "2_2") (pintype "passive"))
    )
    (net (code "61") (name "/A15") (class "Default")
      (node (ref "IC2") (pin "22") (pinfunction "PK7(ADC15/PCINT23)_22") (pintype "bidirectional"))
      (node (ref "SV6") (pin "1") (pinfunction "1_1") (pintype "passive"))
    )
    (net (code "62") (name "/AREF") (class "Default")
      (node (ref "IC2") (pin "46") (pinfunction "AREF_46") (pintype "bidirectional"))
      (node (ref "SV3") (pin "8") (pinfunction "8_8") (pintype "passive"))
    )
    (net (code "63") (name "/MISO") (class "Default")
      (node (ref "IC2") (pin "77") (pinfunction "(MISO/PCINT3)PB3_77") (pintype "bidirectional"))
      (node (ref "NRF") (pin "2") (pinfunction "2_2") (pintype "passive"))
      (node (ref "SV7") (pin "31") (pinfunction "31_31") (pintype "passive"))
    )
    (net (code "64") (name "/MOSI") (class "Default")
      (node (ref "IC2") (pin "78") (pinfunction "(MOSI/PCINT2)PB2_78") (pintype "bidirectional"))
      (node (ref "NRF") (pin "3") (pinfunction "3_3") (pintype "passive"))
      (node (ref "SV7") (pin "32") (pinfunction "32_32") (pintype "passive"))
    )
    (net (code "65") (name "/R0") (class "Default")
      (node (ref "IC2") (pin "31") (pinfunction "(RXD0/PCIN8)PE0_31") (pintype "bidirectional"))
      (node (ref "SV2") (pin "1") (pinfunction "1_1") (pintype "passive"))
    )
    (net (code "66") (name "/R1") (class "Default")
      (node (ref "IC2") (pin "25") (pinfunction "(RXD1/INT2)PD2_25") (pintype "bidirectional"))
      (node (ref "R1") (pin "2") (pinfunction "2_2") (pintype "passive"))
      (node (ref "R2") (pin "1") (pinfunction "1_1") (pintype "passive"))
      (node (ref "SERIAL1") (pin "2") (pinfunction "2_2") (pintype "passive"))
      (node (ref "SV1") (pin "3") (pinfunction "3_3") (pintype "passive"))
    )
    (net (code "67") (name "/R2") (class "Default")
      (node (ref "BLUETOOTH_MODULE") (pin "2") (pinfunction "2_2") (pintype "passive"))
      (node (ref "IC2") (pin "27") (pinfunction "PH0(RXD2)_27") (pintype "bidirectional"))
      (node (ref "SERIAL2") (pin "2") (pinfunction "2_2") (pintype "passive"))
      (node (ref "SV1") (pin "5") (pinfunction "5_5") (pintype "passive"))
    )
    (net (code "68") (name "/R3") (class "Default")
      (node (ref "IC2") (pin "29") (pinfunction "PJ0(RXD3/PCINT9)_29") (pintype "bidirectional"))
      (node (ref "SERIAL3") (pin "2") (pinfunction "2_2") (pintype "passive"))
      (node (ref "SV1") (pin "7") (pinfunction "7_7") (pintype "passive"))
    )
    (net (code "69") (name "/RESET") (class "Default")
      (node (ref "IC2") (pin "1") (pinfunction "~{RESET}_1") (pintype "bidirectional"))
      (node (ref "SV4") (pin "6") (pinfunction "6_6") (pintype "passive"))
    )
    (net (code "70") (name "/SCK") (class "Default")
      (node (ref "IC2") (pin "79") (pinfunction "(SCK/PCINT1)PB1_79") (pintype "bidirectional"))
      (node (ref "NRF") (pin "4") (pinfunction "4_4") (pintype "passive"))
      (node (ref "SV7") (pin "33") (pinfunction "33_33") (pintype "passive"))
    )
    (net (code "71") (name "/SCL") (class "Default")
      (node (ref "IC2") (pin "23") (pinfunction "(SCL/INT0)PD0_23") (pintype "bidirectional"))
      (node (ref "SV1") (pin "1") (pinfunction "1_1") (pintype "passive"))
    )
    (net (code "72") (name "/SDA") (class "Default")
      (node (ref "IC2") (pin "24") (pinfunction "(SDA/INT1)PD1_24") (pintype "bidirectional"))
      (node (ref "SV1") (pin "2") (pinfunction "2_2") (pintype "passive"))
    )
    (net (code "73") (name "/SS") (class "Default")
      (node (ref "IC2") (pin "80") (pinfunction "(SS/PCINT0)PB0_80") (pintype "bidirectional"))
      (node (ref "SV7") (pin "34") (pinfunction "34_34") (pintype "passive"))
    )
    (net (code "74") (name "/T0") (class "Default")
      (node (ref "IC2") (pin "32") (pinfunction "(TXD0)PE1_32") (pintype "bidirectional"))
      (node (ref "SV2") (pin "2") (pinfunction "2_2") (pintype "passive"))
    )
    (net (code "75") (name "/T1") (class "Default")
      (node (ref "ESP8266") (pin "8") (pinfunction "8_8") (pintype "passive"))
      (node (ref "IC2") (pin "26") (pinfunction "(TXD1/INT3)PD3_26") (pintype "bidirectional"))
      (node (ref "SERIAL1") (pin "3") (pinfunction "3_3") (pintype "passive"))
      (node (ref "SV1") (pin "4") (pinfunction "4_4") (pintype "passive"))
    )
    (net (code "76") (name "/T2") (class "Default")
      (node (ref "BLUETOOTH_MODULE") (pin "1") (pinfunction "1_1") (pintype "passive"))
      (node (ref "IC2") (pin "28") (pinfunction "PH1(TXD2)_28") (pintype "bidirectional"))
      (node (ref "SERIAL2") (pin "3") (pinfunction "3_3") (pintype "passive"))
      (node (ref "SV1") (pin "6") (pinfunction "6_6") (pintype "passive"))
    )
    (net (code "77") (name "/T3") (class "Default")
      (node (ref "IC2") (pin "30") (pinfunction "PJ1(TXD3/PCINT10)_30") (pintype "bidirectional"))
      (node (ref "SERIAL3") (pin "3") (pinfunction "3_3") (pintype "passive"))
      (node (ref "SV1") (pin "8") (pinfunction "8_8") (pintype "passive"))
    )
    (net (code "78") (name "/VI") (class "Default")
      (node (ref "IC2") (pin "6") (pinfunction "+VIN_6") (pintype "power_in"))
      (node (ref "SV4") (pin "1") (pinfunction "1_1") (pintype "passive"))
    )
    (net (code "79") (name "/VIN") (class "Default")
      (node (ref "12V") (pin "3") (pinfunction "3_3") (pintype "passive"))
      (node (ref "C2") (pin "1") (pinfunction "1_1") (pintype "passive"))
      (node (ref "C4") (pin "1") (pinfunction "1_1") (pintype "passive"))
      (node (ref "C6") (pin "1") (pinfunction "1_1") (pintype "passive"))
      (node (ref "D1") (pin "C") (pinfunction "C_C") (pintype "passive"))
      (node (ref "D11") (pin "C") (pinfunction "C_C") (pintype "passive"))
      (node (ref "D13") (pin "C") (pinfunction "C_C") (pintype "passive"))
      (node (ref "D14") (pin "C") (pinfunction "C_C") (pintype "passive"))
      (node (ref "D17") (pin "C") (pinfunction "C_C") (pintype "passive"))
      (node (ref "D19") (pin "C") (pinfunction "C_C") (pintype "passive"))
      (node (ref "D21") (pin "C") (pinfunction "C_C") (pintype "passive"))
      (node (ref "D22") (pin "C") (pinfunction "C_C") (pintype "passive"))
      (node (ref "D3") (pin "C") (pinfunction "C_C") (pintype "passive"))
      (node (ref "D5") (pin "C") (pinfunction "C_C") (pintype "passive"))
      (node (ref "D6") (pin "C") (pinfunction "C_C") (pintype "passive"))
      (node (ref "D9") (pin "C") (pinfunction "C_C") (pintype "passive"))
      (node (ref "IC1") (pin "4") (pinfunction "VS_4") (pintype "power_in"))
      (node (ref "IC3") (pin "4") (pinfunction "VS_4") (pintype "power_in"))
      (node (ref "IC4") (pin "4") (pinfunction "VS_4") (pintype "power_in"))
      (node (ref "SENSOR3") (pin "3") (pinfunction "3_3") (pintype "passive"))
      (node (ref "SENSOR4") (pin "3") (pinfunction "3_3") (pintype "passive"))
      (node (ref "SENSOR5") (pin "3") (pinfunction "3_3") (pintype "passive"))
      (node (ref "VIN") (pin "1") (pinfunction "1_1") (pintype "passive"))
    )
    (net (code "80") (name "GND") (class "Default")
      (node (ref "12V") (pin "1") (pinfunction "1_1") (pintype "passive"))
      (node (ref "12V") (pin "2") (pinfunction "2_2") (pintype "passive"))
      (node (ref "24V") (pin "2") (pinfunction "2_2") (pintype "passive"))
      (node (ref "BLUETOOTH_MODULE") (pin "3") (pinfunction "3_3") (pintype "passive"))
      (node (ref "C1") (pin "2") (pinfunction "2_2") (pintype "passive"))
      (node (ref "C2") (pin "2") (pinfunction "2_2") (pintype "passive"))
      (node (ref "C3") (pin "2") (pinfunction "2_2") (pintype "passive"))
      (node (ref "C4") (pin "2") (pinfunction "2_2") (pintype "passive"))
      (node (ref "C5") (pin "2") (pinfunction "2_2") (pintype "passive"))
      (node (ref "C6") (pin "2") (pinfunction "2_2") (pintype "passive"))
      (node (ref "C7") (pin "2") (pinfunction "2_2") (pintype "passive"))
      (node (ref "C8") (pin "2") (pinfunction "2_2") (pintype "passive"))
      (node (ref "D10") (pin "A") (pinfunction "A_A") (pintype "passive"))
      (node (ref "D12") (pin "A") (pinfunction "A_A") (pintype "passive"))
      (node (ref "D15") (pin "A") (pinfunction "A_A") (pintype "passive"))
      (node (ref "D16") (pin "A") (pinfunction "A_A") (pintype "passive"))
      (node (ref "D18") (pin "A") (pinfunction "A_A") (pintype "passive"))
      (node (ref "D2") (pin "A") (pinfunction "A_A") (pintype "passive"))
      (node (ref "D20") (pin "A") (pinfunction "A_A") (pintype "passive"))
      (node (ref "D23") (pin "A") (pinfunction "A_A") (pintype "passive"))
      (node (ref "D24") (pin "A") (pinfunction "A_A") (pintype "passive"))
      (node (ref "D26") (pin "A") (pinfunction "A_A") (pintype "passive"))
      (node (ref "D28") (pin "A") (pinfunction "A_A") (pintype "passive"))
      (node (ref "D31") (pin "A") (pinfunction "A_A") (pintype "passive"))
      (node (ref "D32") (pin "A") (pinfunction "A_A") (pintype "passive"))
      (node (ref "D4") (pin "A") (pinfunction "A_A") (pintype "passive"))
      (node (ref "D7") (pin "A") (pinfunction "A_A") (pintype "passive"))
      (node (ref "D8") (pin "A") (pinfunction "A_A") (pintype "passive"))
      (node (ref "ESP8266") (pin "3") (pinfunction "3_3") (pintype "passive"))
      (node (ref "ESP8266") (pin "7") (pinfunction "7_7") (pintype "passive"))
      (node (ref "GND") (pin "1") (pinfunction "1_1") (pintype "passive"))
      (node (ref "GND") (pin "2") (pinfunction "2_2") (pintype "passive"))
      (node (ref "GND") (pin "3") (pinfunction "3_3") (pintype "passive"))
      (node (ref "IC1") (pin "1") (pinfunction "SEN_A_1") (pintype "input"))
      (node (ref "IC1") (pin "15") (pinfunction "SEN_B_15") (pintype "input"))
      (node (ref "IC1") (pin "8") (pinfunction "GND_8") (pintype "power_in"))
      (node (ref "IC2") (pin "4") (pinfunction "GND_4") (pintype "power_in"))
      (node (ref "IC2") (pin "45") (pinfunction "GND_45") (pintype "power_in"))
      (node (ref "IC2") (pin "5") (pinfunction "GND_5") (pintype "power_in"))
      (node (ref "IC2") (pin "81") (pinfunction "GND_81") (pintype "power_in"))
      (node (ref "IC2") (pin "82") (pinfunction "GND_82") (pintype "power_in"))
      (node (ref "IC3") (pin "1") (pinfunction "SEN_A_1") (pintype "input"))
      (node (ref "IC3") (pin "15") (pinfunction "SEN_B_15") (pintype "input"))
      (node (ref "IC3") (pin "8") (pinfunction "GND_8") (pintype "power_in"))
      (node (ref "IC4") (pin "1") (pinfunction "SEN_A_1") (pintype "input"))
      (node (ref "IC4") (pin "15") (pinfunction "SEN_B_15") (pintype "input"))
      (node (ref "IC4") (pin "8") (pinfunction "GND_8") (pintype "power_in"))
      (node (ref "IC5") (pin "1") (pinfunction "SEN_A_1") (pintype "input"))
      (node (ref "IC5") (pin "15") (pinfunction "SEN_B_15") (pintype "input"))
      (node (ref "IC5") (pin "8") (pinfunction "GND_8") (pintype "power_in"))
      (node (ref "LIMIT_SW1") (pin "2") (pinfunction "2_2") (pintype "passive"))
      (node (ref "LIMIT_SW2") (pin "2") (pinfunction "2_2") (pintype "passive"))
      (node (ref "NRF") (pin "8") (pinfunction "8_8") (pintype "passive"))
      (node (ref "R2") (pin "2") (pinfunction "2_2") (pintype "passive"))
      (node (ref "SENSOR1") (pin "2") (pinfunction "2_2") (pintype "passive"))
      (node (ref "SENSOR2") (pin "2") (pinfunction "2_2") (pintype "passive"))
      (node (ref "SENSOR3") (pin "2") (pinfunction "2_2") (pintype "passive"))
      (node (ref "SENSOR4") (pin "2") (pinfunction "2_2") (pintype "passive"))
      (node (ref "SENSOR5") (pin "2") (pinfunction "2_2") (pintype "passive"))
      (node (ref "SENSOR_SRB") (pin "2") (pinfunction "2_2") (pintype "passive"))
      (node (ref "SENSOR_TT") (pin "2") (pinfunction "2_2") (pintype "passive"))
      (node (ref "SERIAL1") (pin "1") (pinfunction "1_1") (pintype "passive"))
      (node (ref "SERIAL2") (pin "1") (pinfunction "1_1") (pintype "passive"))
      (node (ref "SERIAL3") (pin "1") (pinfunction "1_1") (pintype "passive"))
      (node (ref "SV3") (pin "7") (pinfunction "7_7") (pintype "passive"))
      (node (ref "SV4") (pin "2") (pinfunction "2_2") (pintype "passive"))
      (node (ref "SV4") (pin "3") (pinfunction "3_3") (pintype "passive"))
      (node (ref "SV7") (pin "35") (pinfunction "35_35") (pintype "passive"))
      (node (ref "SV7") (pin "36") (pinfunction "36_36") (pintype "passive"))
      (node (ref "VIN") (pin "2") (pinfunction "2_2") (pintype "passive"))
    )
    (net (code "81") (name "Net-(ESP8266-Pad1)") (class "Default")
      (node (ref "ESP8266") (pin "1") (pinfunction "1_1") (pintype "passive"))
      (node (ref "R1") (pin "1") (pinfunction "1_1") (pintype "passive"))
    )
    (net (code "82") (name "Net-(IC1-OUT1)") (class "Default")
      (node (ref "D1") (pin "A") (pinfunction "A_A") (pintype "passive"))
      (node (ref "D2") (pin "C") (pinfunction "C_C") (pintype "passive"))
      (node (ref "IC1") (pin "2") (pinfunction "OUT1_2") (pintype "output"))
      (node (ref "MOTOR1") (pin "1") (pinfunction "1_1") (pintype "passive"))
    )
    (net (code "83") (name "Net-(IC1-OUT2)") (class "Default")
      (node (ref "D3") (pin "A") (pinfunction "A_A") (pintype "passive"))
      (node (ref "D4") (pin "C") (pinfunction "C_C") (pintype "passive"))
      (node (ref "IC1") (pin "3") (pinfunction "OUT2_3") (pintype "output"))
      (node (ref "MOTOR1") (pin "2") (pinfunction "2_2") (pintype "passive"))
    )
    (net (code "84") (name "Net-(IC1-OUT3)") (class "Default")
      (node (ref "D5") (pin "A") (pinfunction "A_A") (pintype "passive"))
      (node (ref "D7") (pin "C") (pinfunction "C_C") (pintype "passive"))
      (node (ref "IC1") (pin "13") (pinfunction "OUT3_13") (pintype "output"))
      (node (ref "MOTOR2") (pin "1") (pinfunction "1_1") (pintype "passive"))
    )
    (net (code "85") (name "Net-(IC1-OUT4)") (class "Default")
      (node (ref "D6") (pin "A") (pinfunction "A_A") (pintype "passive"))
      (node (ref "D8") (pin "C") (pinfunction "C_C") (pintype "passive"))
      (node (ref "IC1") (pin "14") (pinfunction "OUT4_14") (pintype "output"))
      (node (ref "MOTOR2") (pin "2") (pinfunction "2_2") (pintype "passive"))
    )
    (net (code "86") (name "Net-(IC3-OUT1)") (class "Default")
      (node (ref "D10") (pin "C") (pinfunction "C_C") (pintype "passive"))
      (node (ref "D9") (pin "A") (pinfunction "A_A") (pintype "passive"))
      (node (ref "IC3") (pin "2") (pinfunction "OUT1_2") (pintype "output"))
      (node (ref "MOTOR3") (pin "1") (pinfunction "1_1") (pintype "passive"))
    )
    (net (code "87") (name "Net-(IC3-OUT2)") (class "Default")
      (node (ref "D11") (pin "A") (pinfunction "A_A") (pintype "passive"))
      (node (ref "D12") (pin "C") (pinfunction "C_C") (pintype "passive"))
      (node (ref "IC3") (pin "3") (pinfunction "OUT2_3") (pintype "output"))
      (node (ref "MOTOR3") (pin "2") (pinfunction "2_2") (pintype "passive"))
    )
    (net (code "88") (name "Net-(IC3-OUT3)") (class "Default")
      (node (ref "D13") (pin "A") (pinfunction "A_A") (pintype "passive"))
      (node (ref "D15") (pin "C") (pinfunction "C_C") (pintype "passive"))
      (node (ref "IC3") (pin "13") (pinfunction "OUT3_13") (pintype "output"))
      (node (ref "MOTOR4") (pin "1") (pinfunction "1_1") (pintype "passive"))
    )
    (net (code "89") (name "Net-(IC3-OUT4)") (class "Default")
      (node (ref "D14") (pin "A") (pinfunction "A_A") (pintype "passive"))
      (node (ref "D16") (pin "C") (pinfunction "C_C") (pintype "passive"))
      (node (ref "IC3") (pin "14") (pinfunction "OUT4_14") (pintype "output"))
      (node (ref "MOTOR4") (pin "2") (pinfunction "2_2") (pintype "passive"))
    )
    (net (code "90") (name "Net-(IC4-OUT1)") (class "Default")
      (node (ref "D17") (pin "A") (pinfunction "A_A") (pintype "passive"))
      (node (ref "D18") (pin "C") (pinfunction "C_C") (pintype "passive"))
      (node (ref "IC4") (pin "2") (pinfunction "OUT1_2") (pintype "output"))
      (node (ref "MOTOR5") (pin "1") (pinfunction "1_1") (pintype "passive"))
    )
    (net (code "91") (name "Net-(IC4-OUT2)") (class "Default")
      (node (ref "D19") (pin "A") (pinfunction "A_A") (pintype "passive"))
      (node (ref "D20") (pin "C") (pinfunction "C_C") (pintype "passive"))
      (node (ref "IC4") (pin "3") (pinfunction "OUT2_3") (pintype "output"))
      (node (ref "MOTOR5") (pin "2") (pinfunction "2_2") (pintype "passive"))
    )
    (net (code "92") (name "Net-(IC4-OUT3)") (class "Default")
      (node (ref "D21") (pin "A") (pinfunction "A_A") (pintype "passive"))
      (node (ref "D23") (pin "C") (pinfunction "C_C") (pintype "passive"))
      (node (ref "IC4") (pin "13") (pinfunction "OUT3_13") (pintype "output"))
      (node (ref "MOTOR6") (pin "1") (pinfunction "1_1") (pintype "passive"))
    )
    (net (code "93") (name "Net-(IC4-OUT4)") (class "Default")
      (node (ref "D22") (pin "A") (pinfunction "A_A") (pintype "passive"))
      (node (ref "D24") (pin "C") (pinfunction "C_C") (pintype "passive"))
      (node (ref "IC4") (pin "14") (pinfunction "OUT4_14") (pintype "output"))
      (node (ref "MOTOR6") (pin "2") (pinfunction "2_2") (pintype "passive"))
    )
    (net (code "94") (name "Net-(IC5-OUT1)") (class "Default")
      (node (ref "D25") (pin "A") (pinfunction "A_A") (pintype "passive"))
      (node (ref "D26") (pin "C") (pinfunction "C_C") (pintype "passive"))
      (node (ref "IC5") (pin "2") (pinfunction "OUT1_2") (pintype "output"))
      (node (ref "MOTOR7") (pin "1") (pinfunction "1_1") (pintype "passive"))
    )
    (net (code "95") (name "Net-(IC5-OUT2)") (class "Default")
      (node (ref "D27") (pin "A") (pinfunction "A_A") (pintype "passive"))
      (node (ref "D28") (pin "C") (pinfunction "C_C") (pintype "passive"))
      (node (ref "IC5") (pin "3") (pinfunction "OUT2_3") (pintype "output"))
      (node (ref "MOTOR7") (pin "2") (pinfunction "2_2") (pintype "passive"))
    )
    (net (code "96") (name "Net-(IC5-OUT3)") (class "Default")
      (node (ref "D29") (pin "A") (pinfunction "A_A") (pintype "passive"))
      (node (ref "D31") (pin "C") (pinfunction "C_C") (pintype "passive"))
      (node (ref "IC5") (pin "13") (pinfunction "OUT3_13") (pintype "output"))
      (node (ref "MOTOR8") (pin "1") (pinfunction "1_1") (pintype "passive"))
    )
    (net (code "97") (name "Net-(IC5-OUT4)") (class "Default")
      (node (ref "D30") (pin "A") (pinfunction "A_A") (pintype "passive"))
      (node (ref "D32") (pin "C") (pinfunction "C_C") (pintype "passive"))
      (node (ref "IC5") (pin "14") (pinfunction "OUT4_14") (pintype "output"))
      (node (ref "MOTOR8") (pin "2") (pinfunction "2_2") (pintype "passive"))
    )
    (net (code "98") (name "unconnected-(24V-Pad3)") (class "Default")
      (node (ref "24V") (pin "3") (pinfunction "3_3") (pintype "passive"))
    )
    (net (code "99") (name "unconnected-(ESP8266-Pad4)") (class "Default")
      (node (ref "ESP8266") (pin "4") (pinfunction "4_4") (pintype "passive"))
    )
    (net (code "100") (name "unconnected-(ESP8266-Pad5)") (class "Default")
      (node (ref "ESP8266") (pin "5") (pinfunction "5_5") (pintype "passive"))
    )
    (net (code "101") (name "unconnected-(NRF-Pad1)") (class "Default")
      (node (ref "NRF") (pin "1") (pinfunction "1_1") (pintype "passive"))
    )
    (net (code "102") (name "unconnected-(SV4-Pad7)") (class "Default")
      (node (ref "SV4") (pin "7") (pinfunction "7_7") (pintype "passive"))
    )
    (net (code "103") (name "unconnected-(SV4-Pad8)") (class "Default")
      (node (ref "SV4") (pin "8") (pinfunction "8_8") (pintype "passive"))
    )
    (net (code "104") (name "unconnected-(VIN-Pad3)") (class "Default")
      (node (ref "VIN") (pin "3") (pinfunction "3_3") (pintype "passive"))
    )
  )
)
